# opendeep_pba001_cnc_v01.net
KiCad netlist of a schematic drawn in EasyEDA Pro
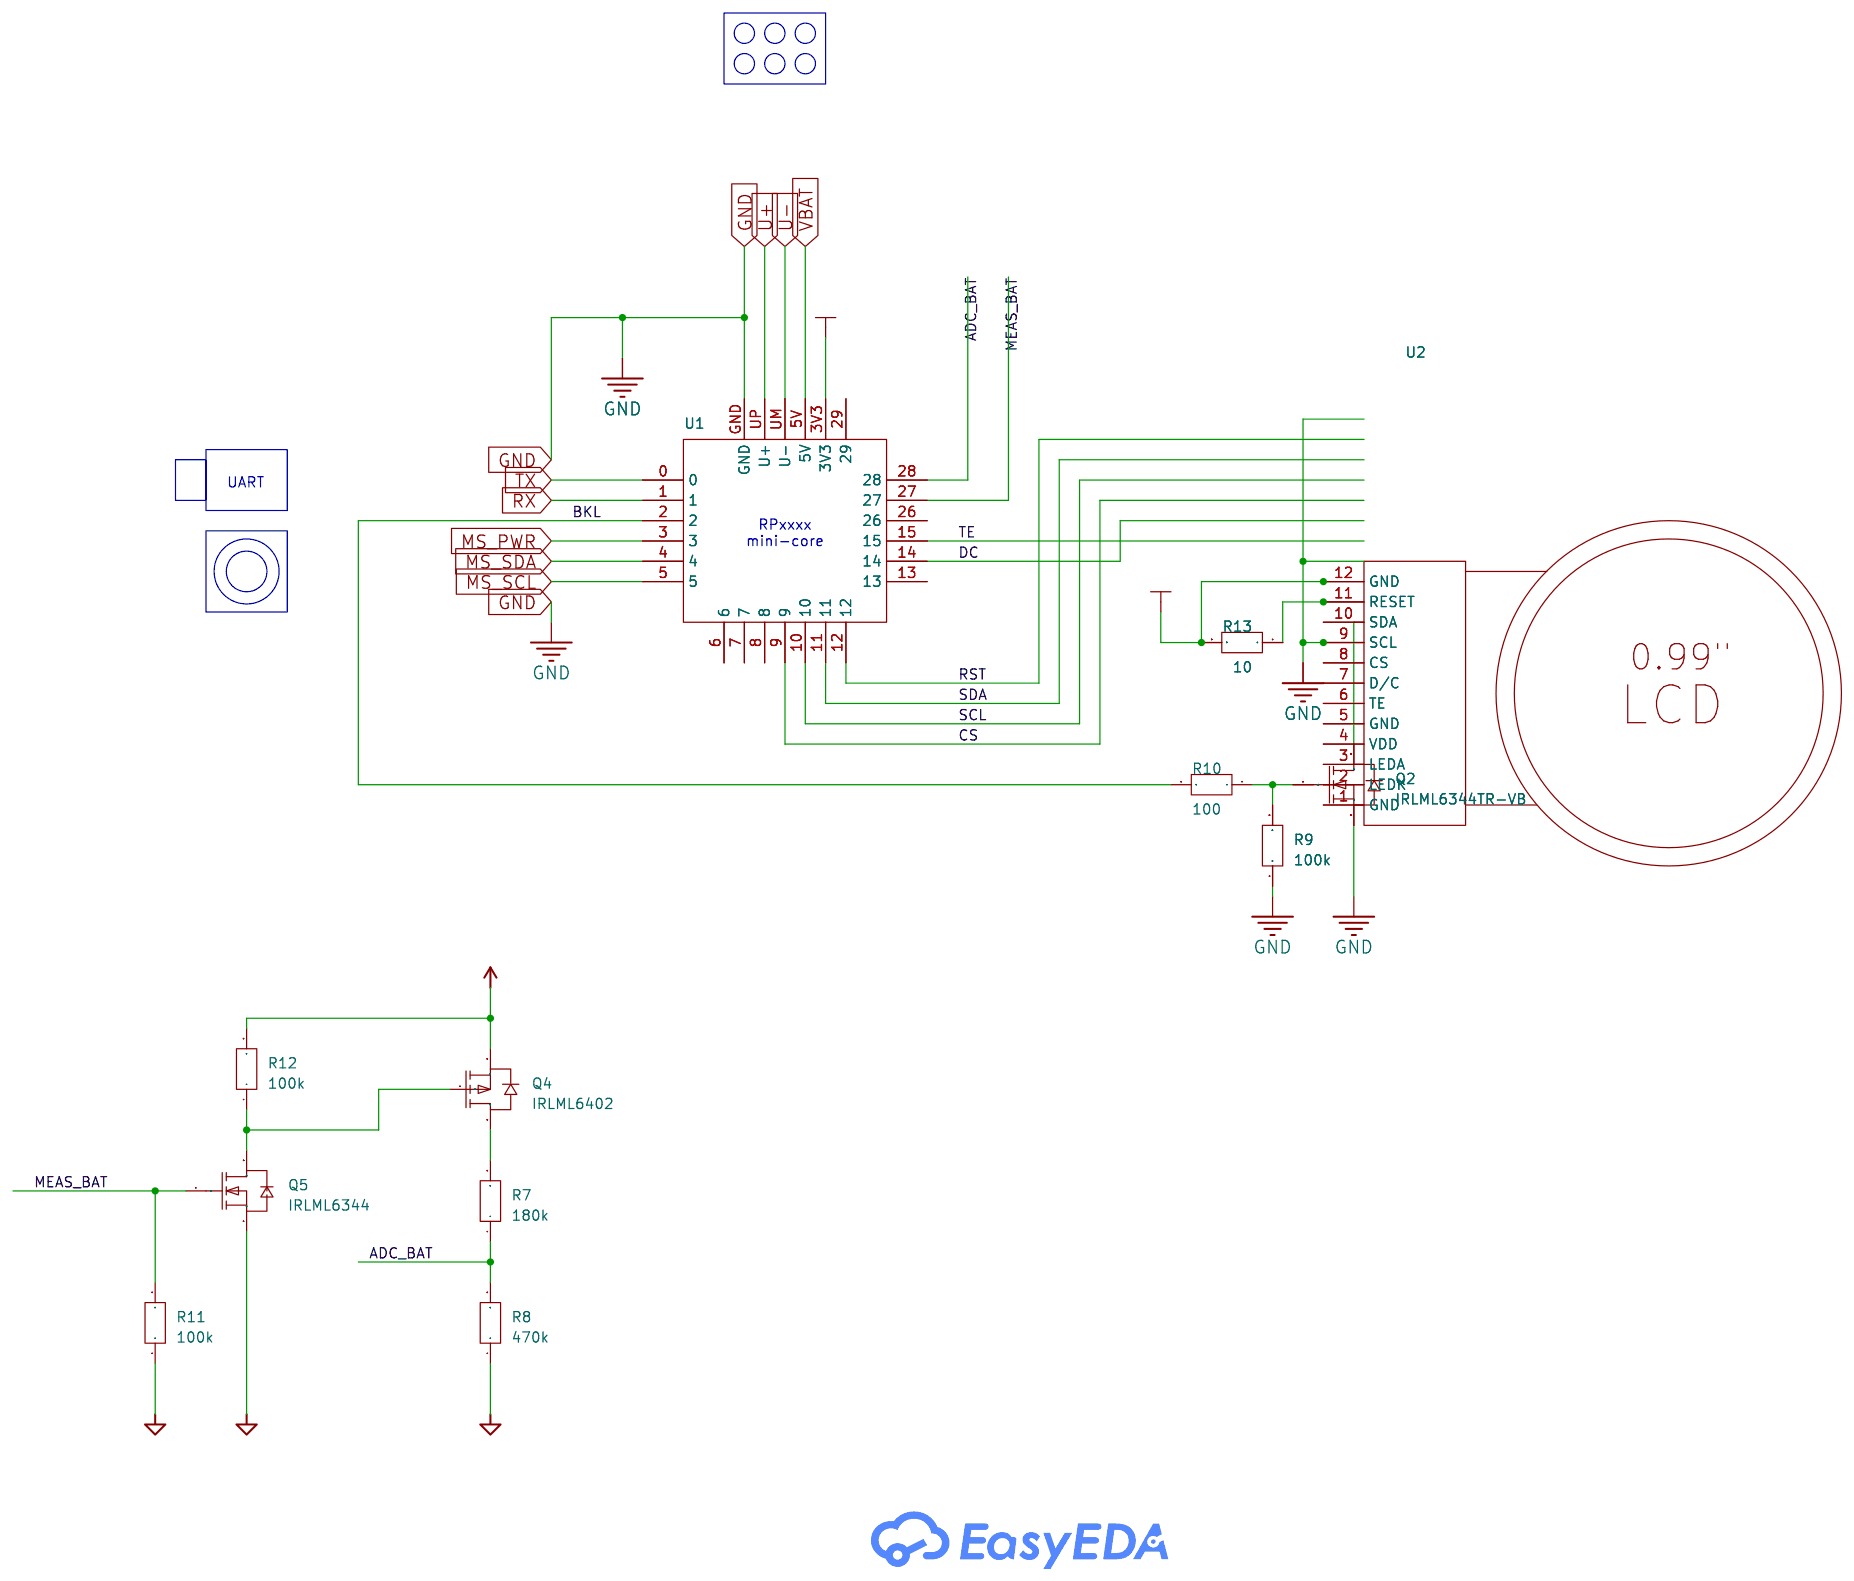
[diagram p0: schematic sheet]

(export (version "E")
  (design (tool "Eeschema 10.0.6"))
  (components
    (comp (ref "Q2")
      (value "IRLML6344TR-VB")
      (footprint "easyedapro:SOT-23-3_L2.9-W1.3-P1.90-LS2.4-BR")
      (fields (field (name "Manufacturer") "VBsemi(微碧半导体)"))
      (libsource (lib "easyedapro") (part "IRLML6344TR"))
    )
    (comp (ref "Q4")
      (value "IRLML6402")
      (footprint "easyedapro:SOT-23-3_L2.9-W1.3-P1.90-LS2.4-BR")
      (fields (field (name "Manufacturer") "TECH PUBLIC(台舟)"))
      (libsource (lib "easyedapro") (part "IRLML6402_C2959853"))
    )
    (comp (ref "Q5")
      (value "IRLML6344")
      (footprint "easyedapro:SOT-23-3_L3.0-W1.7-P0.95-LS2.9-BR")
      (fields (field (name "Manufacturer") "Hottech(合科泰)"))
      (libsource (lib "easyedapro") (part "IRLML6344"))
    )
    (comp (ref "R7")
      (value "180k")
      (footprint "easyedapro:R0603")
      (fields (field (name "Manufacturer Part") "RCC06031K50FKEA") (field (name "Manufacturer") "VISHAY(威世)"))
      (libsource (lib "easyedapro") (part "RCC06031K50FKEA"))
    )
    (comp (ref "R8")
      (value "470k")
      (footprint "easyedapro:R0603")
      (fields (field (name "Manufacturer Part") "RCC06031K50FKEA") (field (name "Manufacturer") "VISHAY(威世)"))
      (libsource (lib "easyedapro") (part "RCC06031K50FKEA"))
    )
    (comp (ref "R9")
      (value "100k")
      (footprint "easyedapro:R0603")
      (fields (field (name "Manufacturer Part") "RCC06031K50FKEA") (field (name "Manufacturer") "VISHAY(威世)"))
      (libsource (lib "easyedapro") (part "RCC06031K50FKEA"))
    )
    (comp (ref "R10")
      (value "100")
      (footprint "easyedapro:R0603")
      (fields (field (name "Manufacturer Part") "RCC06031K50FKEA") (field (name "Manufacturer") "VISHAY(威世)"))
      (libsource (lib "easyedapro") (part "RCC06031K50FKEA"))
    )
    (comp (ref "R11")
      (value "100k")
      (footprint "easyedapro:R0603")
      (fields (field (name "Manufacturer Part") "RCC06031K50FKEA") (field (name "Manufacturer") "VISHAY(威世)"))
      (libsource (lib "easyedapro") (part "RCC06031K50FKEA"))
    )
    (comp (ref "R12")
      (value "100k")
      (footprint "easyedapro:R0603")
      (fields (field (name "Manufacturer Part") "RCC06031K50FKEA") (field (name "Manufacturer") "VISHAY(威世)"))
      (libsource (lib "easyedapro") (part "RCC06031K50FKEA"))
    )
    (comp (ref "R13")
      (value "10")
      (footprint "easyedapro:R0603")
      (fields (field (name "Manufacturer Part") "RCC06031K50FKEA") (field (name "Manufacturer") "VISHAY(威世)"))
      (libsource (lib "easyedapro") (part "RCC06031K50FKEA"))
    )
    (comp (ref "U1")
      (value "~")
      (footprint "easyedapro:PR-mini-core")
      (libsource (lib "easyedapro") (part "RP-mini-core"))
    )
    (comp (ref "U2")
      (value "~")
      (footprint "easyedapro:LCD 0.99")
      (libsource (lib "easyedapro") (part "LCD 0.99"))
    )
  )
  (nets
    (net (code "1") (name "/ADC_BAT") (class "Default")
      (node (ref "R7") (pin "1") (pinfunction "1_1") (pintype "unspecified"))
      (node (ref "R8") (pin "2") (pinfunction "2_2") (pintype "unspecified"))
      (node (ref "U1") (pin "28") (pinfunction "28_28") (pintype "input"))
    )
    (net (code "2") (name "/BKL") (class "Default")
      (node (ref "R10") (pin "2") (pinfunction "2_2") (pintype "unspecified"))
      (node (ref "U1") (pin "2") (pinfunction "2_2") (pintype "input"))
    )
    (net (code "3") (name "/CS") (class "Default")
      (node (ref "U1") (pin "9") (pinfunction "9_9") (pintype "input"))
    )
    (net (code "4") (name "/DC") (class "Default")
      (node (ref "U1") (pin "14") (pinfunction "14_14") (pintype "input"))
    )
    (net (code "5") (name "/MEAS_BAT") (class "Default")
      (node (ref "Q5") (pin "1") (pinfunction "G_1") (pintype "unspecified"))
      (node (ref "R11") (pin "2") (pinfunction "2_2") (pintype "unspecified"))
      (node (ref "U1") (pin "27") (pinfunction "27_27") (pintype "input"))
    )
    (net (code "6") (name "/RST") (class "Default")
      (node (ref "U1") (pin "12") (pinfunction "12_12") (pintype "input"))
    )
    (net (code "7") (name "/SCL") (class "Default")
      (node (ref "U1") (pin "10") (pinfunction "10_10") (pintype "input"))
    )
    (net (code "8") (name "/SDA") (class "Default")
      (node (ref "U1") (pin "11") (pinfunction "11_11") (pintype "input"))
    )
    (net (code "9") (name "/TE") (class "Default")
      (node (ref "U1") (pin "15") (pinfunction "15_15") (pintype "input"))
    )
    (net (code "10") (name "3V3") (class "Default")
      (node (ref "R13") (pin "2") (pinfunction "2_2") (pintype "unspecified"))
      (node (ref "U1") (pin "3V3") (pinfunction "3V3_3V3") (pintype "input"))
      (node (ref "U2") (pin "12") (pinfunction "GND_12") (pintype "input"))
    )
    (net (code "11") (name "GND") (class "Default")
      (node (ref "Q2") (pin "2") (pinfunction "S_2") (pintype "unspecified"))
      (node (ref "Q5") (pin "2") (pinfunction "S_2") (pintype "unspecified"))
      (node (ref "R11") (pin "1") (pinfunction "1_1") (pintype "unspecified"))
      (node (ref "R8") (pin "1") (pinfunction "1_1") (pintype "unspecified"))
      (node (ref "R9") (pin "1") (pinfunction "1_1") (pintype "unspecified"))
      (node (ref "U1") (pin "GND") (pinfunction "GND_GND") (pintype "input"))
      (node (ref "U2") (pin "9") (pinfunction "SCL_9") (pintype "input"))
    )
    (net (code "12") (name "MS_PWR") (class "Default")
      (node (ref "U1") (pin "3") (pinfunction "3_3") (pintype "input"))
    )
    (net (code "13") (name "MS_SCL") (class "Default")
      (node (ref "U1") (pin "5") (pinfunction "5_5") (pintype "input"))
    )
    (net (code "14") (name "MS_SDA") (class "Default")
      (node (ref "U1") (pin "4") (pinfunction "4_4") (pintype "input"))
    )
    (net (code "15") (name "Net-(Q2-G)") (class "Default")
      (node (ref "Q2") (pin "1") (pinfunction "G_1") (pintype "unspecified"))
      (node (ref "R10") (pin "1") (pinfunction "1_1") (pintype "unspecified"))
      (node (ref "R9") (pin "2") (pinfunction "2_2") (pintype "unspecified"))
    )
    (net (code "16") (name "Net-(Q4-D)") (class "Default")
      (node (ref "Q4") (pin "3") (pinfunction "D_3") (pintype "unspecified"))
      (node (ref "R7") (pin "2") (pinfunction "2_2") (pintype "unspecified"))
    )
    (net (code "17") (name "Net-(Q4-G)") (class "Default")
      (node (ref "Q4") (pin "1") (pinfunction "G_1") (pintype "unspecified"))
      (node (ref "Q5") (pin "3") (pinfunction "D_3") (pintype "unspecified"))
      (node (ref "R12") (pin "1") (pinfunction "1_1") (pintype "unspecified"))
    )
    (net (code "18") (name "Net-(U2-RESET)") (class "Default")
      (node (ref "R13") (pin "1") (pinfunction "1_1") (pintype "unspecified"))
      (node (ref "U2") (pin "11") (pinfunction "RESET_11") (pintype "input"))
    )
    (net (code "19") (name "RX") (class "Default")
      (node (ref "U1") (pin "1") (pinfunction "1_1") (pintype "input"))
    )
    (net (code "20") (name "TX") (class "Default")
      (node (ref "U1") (pin "0") (pinfunction "0_0") (pintype "input"))
    )
    (net (code "21") (name "U+") (class "Default")
      (node (ref "U1") (pin "UP") (pinfunction "U+_UP") (pintype "input"))
    )
    (net (code "22") (name "U-") (class "Default")
      (node (ref "U1") (pin "UM") (pinfunction "U-_UM") (pintype "input"))
    )
    (net (code "23") (name "VBAT") (class "Default")
      (node (ref "Q4") (pin "2") (pinfunction "S_2") (pintype "unspecified"))
      (node (ref "R12") (pin "2") (pinfunction "2_2") (pintype "unspecified"))
      (node (ref "U1") (pin "5V") (pinfunction "5V_5V") (pintype "input"))
    )
    (net (code "24") (name "unconnected-(Q2-D-Pad3)") (class "Default")
      (node (ref "Q2") (pin "3") (pinfunction "D_3") (pintype "unspecified"))
    )
    (net (code "25") (name "unconnected-(U1-Pad6)") (class "Default")
      (node (ref "U1") (pin "6") (pinfunction "6_6") (pintype "input"))
    )
    (net (code "26") (name "unconnected-(U1-Pad7)") (class "Default")
      (node (ref "U1") (pin "7") (pinfunction "7_7") (pintype "input"))
    )
    (net (code "27") (name "unconnected-(U1-Pad8)") (class "Default")
      (node (ref "U1") (pin "8") (pinfunction "8_8") (pintype "input"))
    )
    (net (code "28") (name "unconnected-(U1-Pad13)") (class "Default")
      (node (ref "U1") (pin "13") (pinfunction "13_13") (pintype "input"))
    )
    (net (code "29") (name "unconnected-(U1-Pad26)") (class "Default")
      (node (ref "U1") (pin "26") (pinfunction "26_26") (pintype "input"))
    )
    (net (code "30") (name "unconnected-(U1-Pad29)") (class "Default")
      (node (ref "U1") (pin "29") (pinfunction "29_29") (pintype "input"))
    )
    (net (code "31") (name "unconnected-(U2-CS-Pad8)") (class "Default")
      (node (ref "U2") (pin "8") (pinfunction "CS_8") (pintype "input"))
    )
    (net (code "32") (name "unconnected-(U2-D{slash}C-Pad7)") (class "Default")
      (node (ref "U2") (pin "7") (pinfunction "D/C_7") (pintype "input"))
    )
    (net (code "33") (name "unconnected-(U2-GND-Pad1)") (class "Default")
      (node (ref "U2") (pin "1") (pinfunction "GND_1") (pintype "input"))
    )
    (net (code "34") (name "unconnected-(U2-GND-Pad5)") (class "Default")
      (node (ref "U2") (pin "5") (pinfunction "GND_5") (pintype "input"))
    )
    (net (code "35") (name "unconnected-(U2-LEDA-Pad3)") (class "Default")
      (node (ref "U2") (pin "3") (pinfunction "LEDA_3") (pintype "input"))
    )
    (net (code "36") (name "unconnected-(U2-LEDK-Pad2)") (class "Default")
      (node (ref "U2") (pin "2") (pinfunction "LEDK_2") (pintype "input"))
    )
    (net (code "37") (name "unconnected-(U2-SDA-Pad10)") (class "Default")
      (node (ref "U2") (pin "10") (pinfunction "SDA_10") (pintype "input"))
    )
    (net (code "38") (name "unconnected-(U2-TE-Pad6)") (class "Default")
      (node (ref "U2") (pin "6") (pinfunction "TE_6") (pintype "input"))
    )
    (net (code "39") (name "unconnected-(U2-VDD-Pad4)") (class "Default")
      (node (ref "U2") (pin "4") (pinfunction "VDD_4") (pintype "input"))
    )
  )
)
